# TDFN33-10.net
KiCad netlist of a schematic drawn in EAGLE
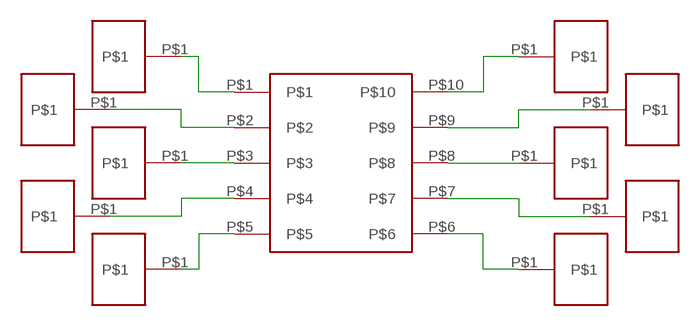
[diagram p0: schematic, sheet 1]

(export (version "E")
  (design (tool "Eeschema 10.0.6"))
  (components
    (comp (ref "U$1")
      (value "TDFN33-10TDFN33-10")
      (footprint "eagle-import:TDFN33-10")
      (libsource (lib "eagle-import") (part "TDFN33-10TDFN33-10"))
    )
    (comp (ref "U$2")
      (value "PAD50X100MIL")
      (footprint "eagle-import:100X50MIL_PAD")
      (libsource (lib "eagle-import") (part "PAD50X100MIL"))
    )
    (comp (ref "U$3")
      (value "PAD50X100MIL")
      (footprint "eagle-import:100X50MIL_PAD")
      (libsource (lib "eagle-import") (part "PAD50X100MIL"))
    )
    (comp (ref "U$4")
      (value "PAD50X100MIL")
      (footprint "eagle-import:100X50MIL_PAD")
      (libsource (lib "eagle-import") (part "PAD50X100MIL"))
    )
    (comp (ref "U$5")
      (value "PAD50X100MIL")
      (footprint "eagle-import:100X50MIL_PAD")
      (libsource (lib "eagle-import") (part "PAD50X100MIL"))
    )
    (comp (ref "U$6")
      (value "PAD50X100MIL")
      (footprint "eagle-import:100X50MIL_PAD")
      (libsource (lib "eagle-import") (part "PAD50X100MIL"))
    )
    (comp (ref "U$7")
      (value "PAD50X100MIL")
      (footprint "eagle-import:100X50MIL_PAD")
      (libsource (lib "eagle-import") (part "PAD50X100MIL"))
    )
    (comp (ref "U$8")
      (value "PAD50X100MIL")
      (footprint "eagle-import:100X50MIL_PAD")
      (libsource (lib "eagle-import") (part "PAD50X100MIL"))
    )
    (comp (ref "U$9")
      (value "PAD50X100MIL")
      (footprint "eagle-import:100X50MIL_PAD")
      (libsource (lib "eagle-import") (part "PAD50X100MIL"))
    )
    (comp (ref "U$10")
      (value "PAD50X100MIL")
      (footprint "eagle-import:100X50MIL_PAD")
      (libsource (lib "eagle-import") (part "PAD50X100MIL"))
    )
    (comp (ref "U$11")
      (value "PAD50X100MIL")
      (footprint "eagle-import:100X50MIL_PAD")
      (libsource (lib "eagle-import") (part "PAD50X100MIL"))
    )
  )
  (nets
    (net (code "1") (name "Net-(U$1-PadP$1)") (class "Default")
      (node (ref "U$1") (pin "P$1") (pinfunction "P$1_P$1") (pintype "bidirectional"))
      (node (ref "U$5") (pin "P$1") (pinfunction "P$1_P$1") (pintype "bidirectional"))
    )
    (net (code "2") (name "Net-(U$1-PadP$2)") (class "Default")
      (node (ref "U$1") (pin "P$2") (pinfunction "P$2_P$2") (pintype "bidirectional"))
      (node (ref "U$3") (pin "P$1") (pinfunction "P$1_P$1") (pintype "bidirectional"))
    )
    (net (code "3") (name "Net-(U$1-PadP$3)") (class "Default")
      (node (ref "U$1") (pin "P$3") (pinfunction "P$3_P$3") (pintype "bidirectional"))
      (node (ref "U$2") (pin "P$1") (pinfunction "P$1_P$1") (pintype "bidirectional"))
    )
    (net (code "4") (name "Net-(U$1-PadP$4)") (class "Default")
      (node (ref "U$1") (pin "P$4") (pinfunction "P$4_P$4") (pintype "bidirectional"))
      (node (ref "U$4") (pin "P$1") (pinfunction "P$1_P$1") (pintype "bidirectional"))
    )
    (net (code "5") (name "Net-(U$1-PadP$5)") (class "Default")
      (node (ref "U$1") (pin "P$5") (pinfunction "P$5_P$5") (pintype "bidirectional"))
      (node (ref "U$6") (pin "P$1") (pinfunction "P$1_P$1") (pintype "bidirectional"))
    )
    (net (code "6") (name "Net-(U$1-PadP$6)") (class "Default")
      (node (ref "U$1") (pin "P$6") (pinfunction "P$6_P$6") (pintype "bidirectional"))
      (node (ref "U$11") (pin "P$1") (pinfunction "P$1_P$1") (pintype "bidirectional"))
    )
    (net (code "7") (name "Net-(U$1-PadP$7)") (class "Default")
      (node (ref "U$1") (pin "P$7") (pinfunction "P$7_P$7") (pintype "bidirectional"))
      (node (ref "U$9") (pin "P$1") (pinfunction "P$1_P$1") (pintype "bidirectional"))
    )
    (net (code "8") (name "Net-(U$1-PadP$8)") (class "Default")
      (node (ref "U$1") (pin "P$8") (pinfunction "P$8_P$8") (pintype "bidirectional"))
      (node (ref "U$7") (pin "P$1") (pinfunction "P$1_P$1") (pintype "bidirectional"))
    )
    (net (code "9") (name "Net-(U$1-PadP$9)") (class "Default")
      (node (ref "U$1") (pin "P$9") (pinfunction "P$9_P$9") (pintype "bidirectional"))
      (node (ref "U$8") (pin "P$1") (pinfunction "P$1_P$1") (pintype "bidirectional"))
    )
    (net (code "10") (name "Net-(U$1-PadP$10)") (class "Default")
      (node (ref "U$1") (pin "P$10") (pinfunction "P$10_P$10") (pintype "bidirectional"))
      (node (ref "U$10") (pin "P$1") (pinfunction "P$1_P$1") (pintype "bidirectional"))
    )
  )
)
